# BT_AQ_DOL_R4.net
KiCad netlist of a schematic drawn in EAGLE
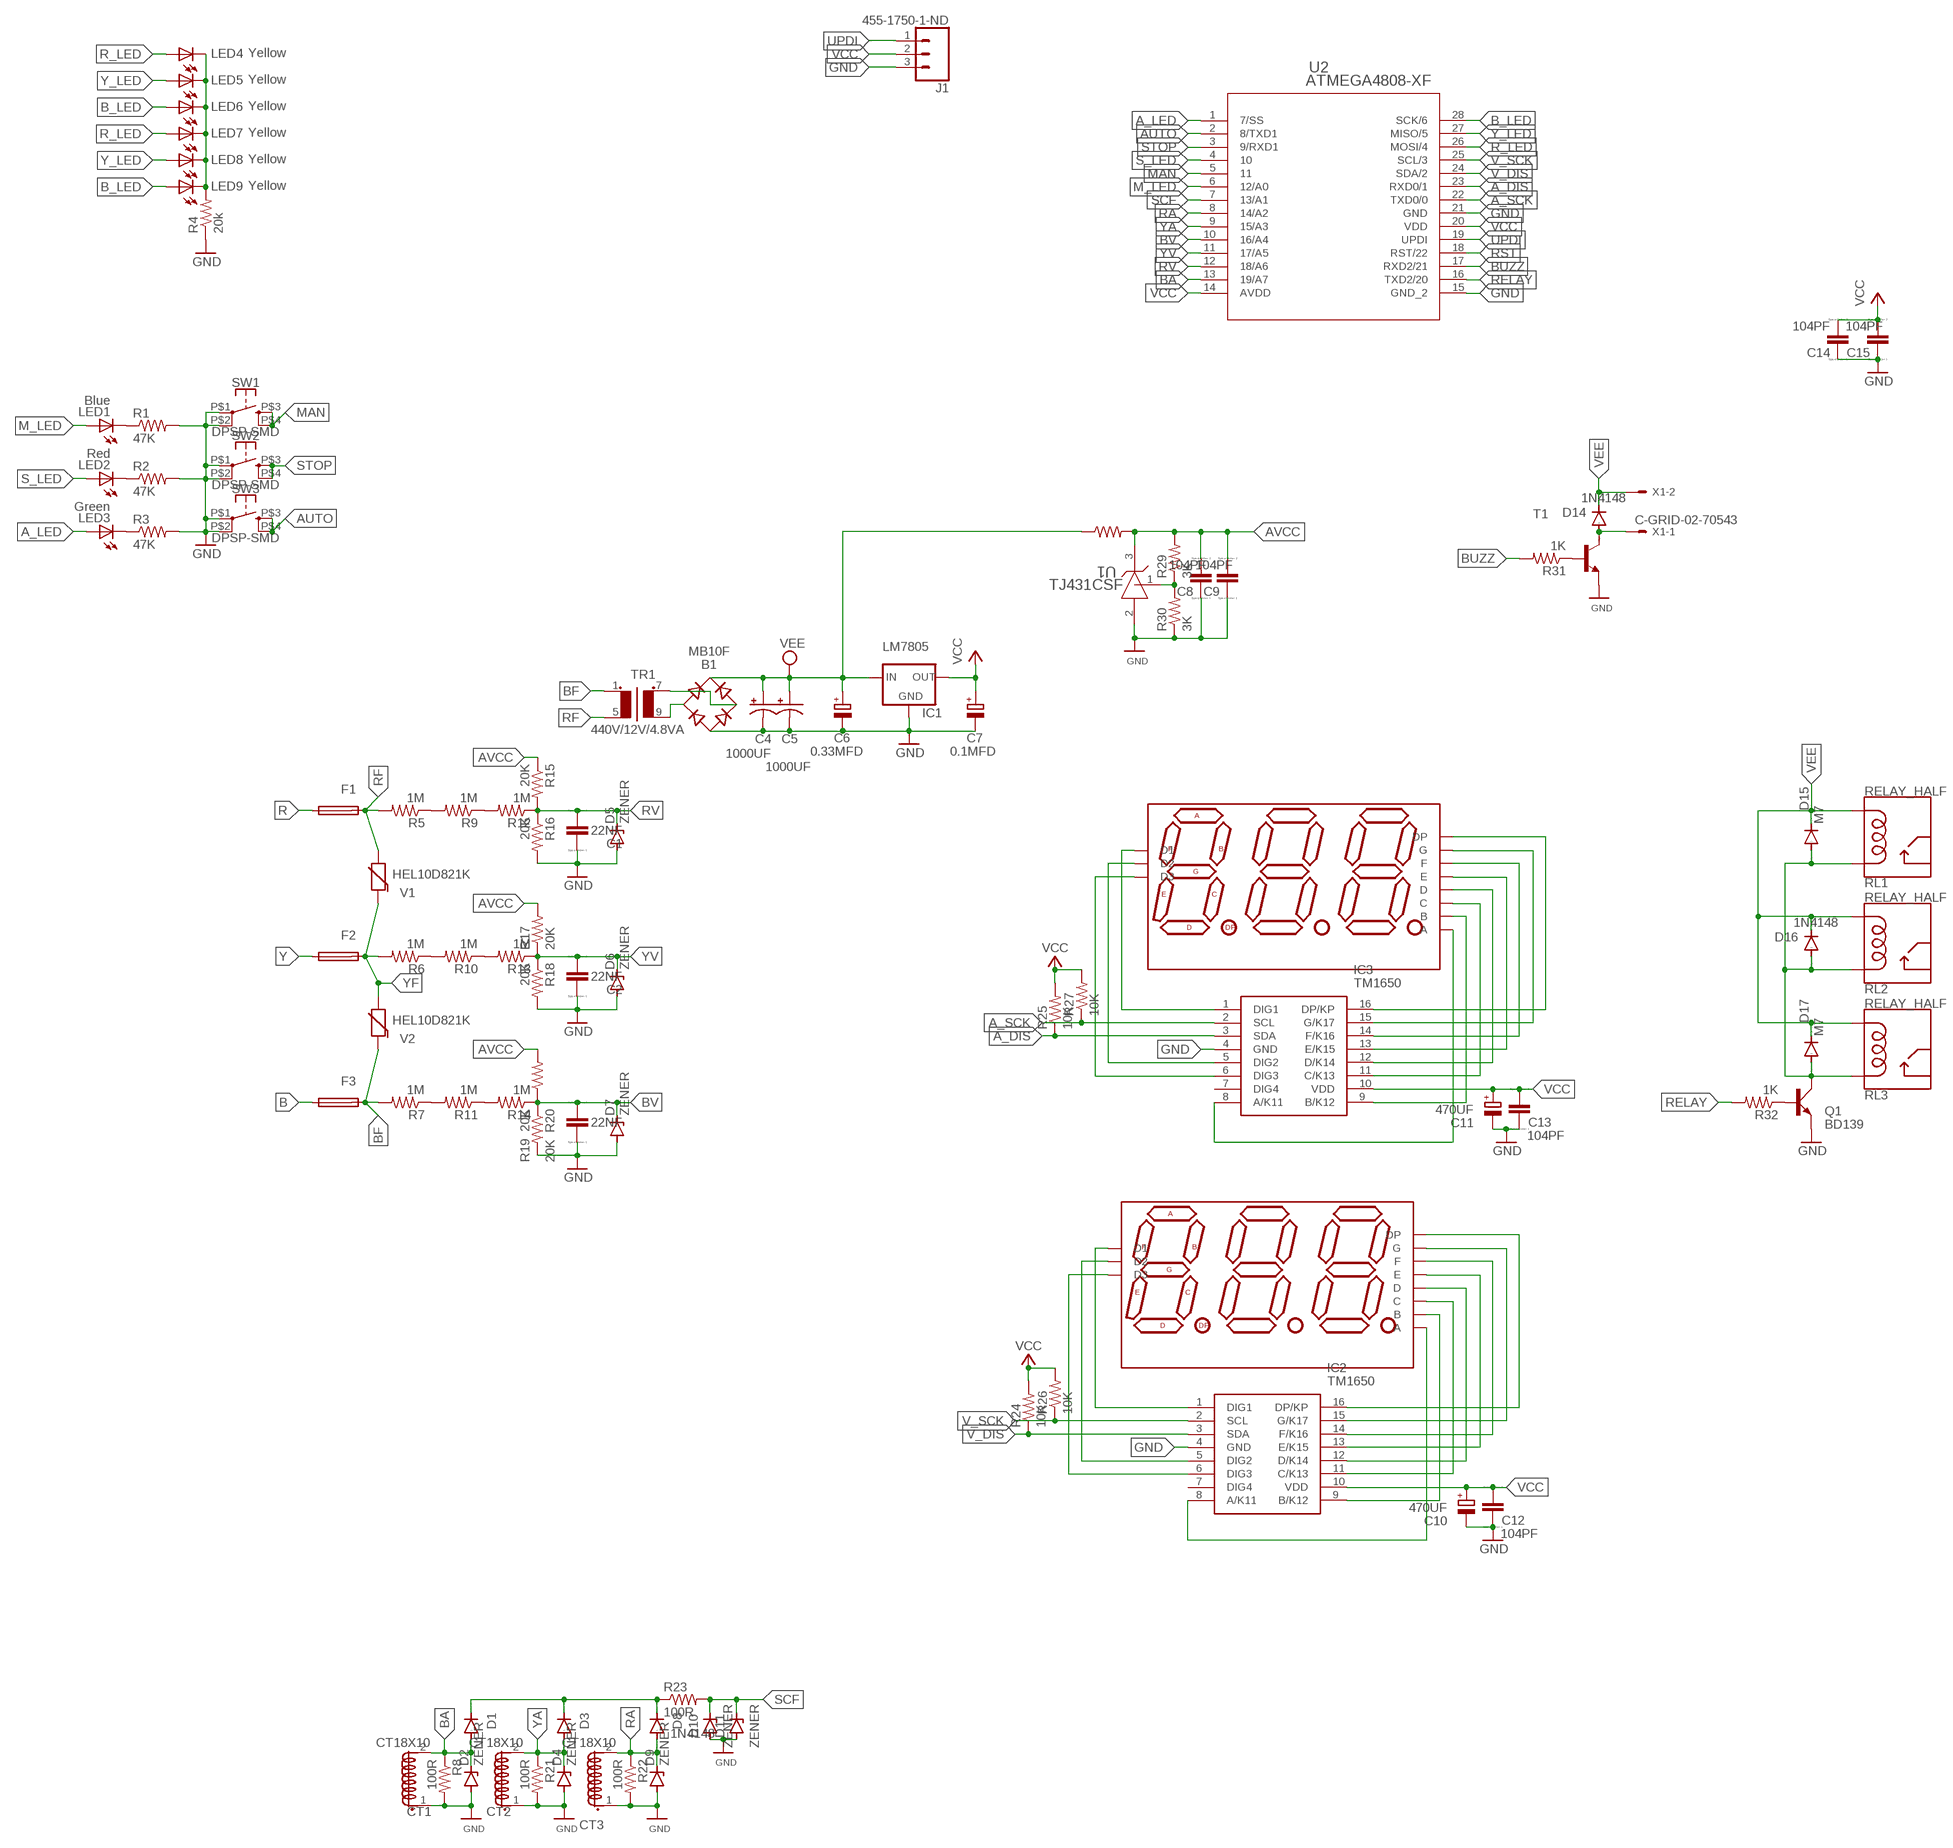
[diagram p0: schematic, sheet 1]

(export (version "E")
  (design (tool "Eeschema 10.0.6"))
  (components
    (comp (ref "B1")
      (value "MB10F")
      (footprint "eagle-import:SOIC-4")
      (libsource (lib "eagle-import") (part "MBS8"))
    )
    (comp (ref "C1")
      (value "22NF")
      (footprint "eagle-import:C1206")
      (libsource (lib "eagle-import") (part "CC1206"))
    )
    (comp (ref "C2")
      (value "22NF")
      (footprint "eagle-import:C1206")
      (libsource (lib "eagle-import") (part "CC1206"))
    )
    (comp (ref "C3")
      (value "22NF")
      (footprint "eagle-import:C1206")
      (libsource (lib "eagle-import") (part "CC1206"))
    )
    (comp (ref "C4")
      (value "1000UF")
      (footprint "eagle-import:E3,5-10")
      (libsource (lib "eagle-import") (part "CPOL-USE3.5-10"))
    )
    (comp (ref "C5")
      (value "1000UF")
      (footprint "eagle-import:E3,5-10")
      (libsource (lib "eagle-import") (part "CPOL-USE3.5-10"))
    )
    (comp (ref "C6")
      (value "0.33MFD")
      (footprint "eagle-import:E2,5-5")
      (libsource (lib "eagle-import") (part "CPOL-EUE2.5-5"))
    )
    (comp (ref "C7")
      (value "0.1MFD")
      (footprint "eagle-import:E2,5-5")
      (libsource (lib "eagle-import") (part "CPOL-EUE2.5-5"))
    )
    (comp (ref "C8")
      (value "104PF")
      (footprint "eagle-import:C1206")
      (libsource (lib "eagle-import") (part "CC1206"))
    )
    (comp (ref "C9")
      (value "104PF")
      (footprint "eagle-import:C1206")
      (libsource (lib "eagle-import") (part "CC1206"))
    )
    (comp (ref "C10")
      (value "470UF")
      (footprint "eagle-import:E3,5-8")
      (libsource (lib "eagle-import") (part "CPOL-EUE3.5-8"))
    )
    (comp (ref "C11")
      (value "470UF")
      (footprint "eagle-import:E3,5-8")
      (libsource (lib "eagle-import") (part "CPOL-EUE3.5-8"))
    )
    (comp (ref "C12")
      (value "104PF")
      (footprint "eagle-import:C1206")
      (libsource (lib "eagle-import") (part "CC1206"))
    )
    (comp (ref "C13")
      (value "104PF")
      (footprint "eagle-import:C1206")
      (libsource (lib "eagle-import") (part "CC1206"))
    )
    (comp (ref "C14")
      (value "104PF")
      (footprint "eagle-import:C1206")
      (libsource (lib "eagle-import") (part "CC1206"))
    )
    (comp (ref "C15")
      (value "104PF")
      (footprint "eagle-import:C1206")
      (libsource (lib "eagle-import") (part "CC1206"))
    )
    (comp (ref "CT1")
      (value "CT18X10")
      (footprint "eagle-import:ZMCT103C")
      (libsource (lib "eagle-import") (part "CT18X10"))
    )
    (comp (ref "CT2")
      (value "CT18X10")
      (footprint "eagle-import:ZMCT103C")
      (libsource (lib "eagle-import") (part "CT18X10"))
    )
    (comp (ref "CT3")
      (value "CT18X10")
      (footprint "eagle-import:ZMCT103C")
      (libsource (lib "eagle-import") (part "CT18X10"))
    )
    (comp (ref "D1")
      (value "1N4148")
      (footprint "eagle-import:MINIMELF")
      (libsource (lib "eagle-import") (part "DIODE-MINIMELF"))
    )
    (comp (ref "D2")
      (value "ZENER")
      (footprint "eagle-import:SOD6126X350")
      (libsource (lib "eagle-import") (part "ZENER_DO-215-BA_"))
    )
    (comp (ref "D3")
      (value "1N4148")
      (footprint "eagle-import:MINIMELF")
      (libsource (lib "eagle-import") (part "DIODE-MINIMELF"))
    )
    (comp (ref "D4")
      (value "ZENER")
      (footprint "eagle-import:SOD6126X350")
      (libsource (lib "eagle-import") (part "ZENER_DO-215-BA_"))
    )
    (comp (ref "D5")
      (value "ZENER")
      (footprint "eagle-import:SOD6126X350")
      (libsource (lib "eagle-import") (part "ZENER_DO-215-BA_"))
    )
    (comp (ref "D6")
      (value "ZENER")
      (footprint "eagle-import:SOD6126X350")
      (libsource (lib "eagle-import") (part "ZENER_DO-215-BA_"))
    )
    (comp (ref "D7")
      (value "ZENER")
      (footprint "eagle-import:SOD6126X350")
      (libsource (lib "eagle-import") (part "ZENER_DO-215-BA_"))
    )
    (comp (ref "D8")
      (value "1N4148")
      (footprint "eagle-import:MINIMELF")
      (libsource (lib "eagle-import") (part "DIODE-MINIMELF"))
    )
    (comp (ref "D9")
      (value "ZENER")
      (footprint "eagle-import:SOD6126X350")
      (libsource (lib "eagle-import") (part "ZENER_DO-215-BA_"))
    )
    (comp (ref "D10")
      (value "ZENER")
      (footprint "eagle-import:SOD6126X350")
      (libsource (lib "eagle-import") (part "ZENER_DO-215-BA_"))
    )
    (comp (ref "D11")
      (value "ZENER")
      (footprint "eagle-import:DIOMELF3516")
      (libsource (lib "eagle-import") (part "ZENER_DO-213AA(SOD-80)_"))
    )
    (comp (ref "D12")
      (value "SUNR036CC3D")
      (footprint "eagle-import:7S3D036_DIP")
      (libsource (lib "eagle-import") (part "7SEGMENT-3DIGITDIP"))
    )
    (comp (ref "D13")
      (value "SUNR036CC3D")
      (footprint "eagle-import:7S3D036_DIP")
      (libsource (lib "eagle-import") (part "7SEGMENT-3DIGITDIP"))
    )
    (comp (ref "D14")
      (value "1N4148")
      (footprint "eagle-import:MINIMELF")
      (libsource (lib "eagle-import") (part "DIODE-MINIMELF"))
    )
    (comp (ref "D15")
      (value "M7")
      (footprint "eagle-import:DO-214AC")
      (libsource (lib "eagle-import") (part "DIODE-DO-214AC"))
    )
    (comp (ref "D16")
      (value "1N4148")
      (footprint "eagle-import:MINIMELF")
      (libsource (lib "eagle-import") (part "DIODE-MINIMELF"))
    )
    (comp (ref "D17")
      (value "M7")
      (footprint "eagle-import:DO-214AC")
      (libsource (lib "eagle-import") (part "DIODE-DO-214AC"))
    )
    (comp (ref "F1")
      (value "TRF600-150")
      (footprint "eagle-import:TRF600-150")
      (libsource (lib "eagle-import") (part "PPTCPTH"))
    )
    (comp (ref "F2")
      (value "TRF600-150")
      (footprint "eagle-import:TRF600-150")
      (libsource (lib "eagle-import") (part "PPTCPTH"))
    )
    (comp (ref "F3")
      (value "TRF600-150")
      (footprint "eagle-import:TRF600-150")
      (libsource (lib "eagle-import") (part "PPTCPTH"))
    )
    (comp (ref "IC1")
      (value "LM7805")
      (footprint "eagle-import:78XXS")
      (libsource (lib "eagle-import") (part "78XXS"))
    )
    (comp (ref "IC2")
      (value "TM1650")
      (footprint "eagle-import:SOIC127P604X185-16N")
      (fields (field (name "MANUFACTURER_PART_NUMBER") "tm1650"))
      (libsource (lib "eagle-import") (part "TM1650"))
    )
    (comp (ref "IC3")
      (value "TM1650")
      (footprint "eagle-import:SOIC127P604X185-16N")
      (fields (field (name "MANUFACTURER_PART_NUMBER") "tm1650"))
      (libsource (lib "eagle-import") (part "TM1650"))
    )
    (comp (ref "J1")
      (value "455-1750-1-ND")
      (footprint "eagle-import:1X03")
      (libsource (lib "eagle-import") (part "CONN_03"))
    )
    (comp (ref "LED1")
      (value "Blue")
      (footprint "eagle-import:LED3MM")
      (libsource (lib "eagle-import") (part "LED3MM"))
    )
    (comp (ref "LED2")
      (value "Red")
      (footprint "eagle-import:LED3MM")
      (libsource (lib "eagle-import") (part "LED3MM"))
    )
    (comp (ref "LED3")
      (value "Green")
      (footprint "eagle-import:LED3MM")
      (libsource (lib "eagle-import") (part "LED3MM"))
    )
    (comp (ref "LED4")
      (value "Yellow")
      (footprint "eagle-import:LED3MM")
      (libsource (lib "eagle-import") (part "LED3MM"))
    )
    (comp (ref "LED5")
      (value "Yellow")
      (footprint "eagle-import:LED3MM")
      (libsource (lib "eagle-import") (part "LED3MM"))
    )
    (comp (ref "LED6")
      (value "Yellow")
      (footprint "eagle-import:LED3MM")
      (libsource (lib "eagle-import") (part "LED3MM"))
    )
    (comp (ref "LED7")
      (value "Yellow")
      (footprint "eagle-import:LED3MM")
      (libsource (lib "eagle-import") (part "LED3MM"))
    )
    (comp (ref "LED8")
      (value "Yellow")
      (footprint "eagle-import:LED3MM")
      (libsource (lib "eagle-import") (part "LED3MM"))
    )
    (comp (ref "LED9")
      (value "Yellow")
      (footprint "eagle-import:LED3MM")
      (libsource (lib "eagle-import") (part "LED3MM"))
    )
    (comp (ref "Q1")
      (value "BD139")
      (footprint "eagle-import:TO126AV")
      (libsource (lib "eagle-import") (part "BD139"))
    )
    (comp (ref "R1")
      (value "47K")
      (footprint "eagle-import:M1206")
      (libsource (lib "eagle-import") (part "rcl_334_R-US_M1206"))
    )
    (comp (ref "R2")
      (value "47K")
      (footprint "eagle-import:M1206")
      (libsource (lib "eagle-import") (part "rcl_334_R-US_M1206"))
    )
    (comp (ref "R3")
      (value "47K")
      (footprint "eagle-import:M1206")
      (libsource (lib "eagle-import") (part "rcl_334_R-US_M1206"))
    )
    (comp (ref "R4")
      (value "20k")
      (footprint "eagle-import:M1206")
      (libsource (lib "eagle-import") (part "rcl_334_R-US_M1206"))
    )
    (comp (ref "R5")
      (value "1M")
      (footprint "eagle-import:M1206")
      (libsource (lib "eagle-import") (part "rcl_334_R-US_M1206"))
    )
    (comp (ref "R6")
      (value "1M")
      (footprint "eagle-import:M1206")
      (libsource (lib "eagle-import") (part "rcl_334_R-US_M1206"))
    )
    (comp (ref "R7")
      (value "1M")
      (footprint "eagle-import:M1206")
      (libsource (lib "eagle-import") (part "rcl_334_R-US_M1206"))
    )
    (comp (ref "R8")
      (value "100R")
      (footprint "eagle-import:M1206")
      (libsource (lib "eagle-import") (part "R-US_M1206"))
    )
    (comp (ref "R9")
      (value "1M")
      (footprint "eagle-import:M1206")
      (libsource (lib "eagle-import") (part "rcl_334_R-US_M1206"))
    )
    (comp (ref "R10")
      (value "1M")
      (footprint "eagle-import:M1206")
      (libsource (lib "eagle-import") (part "rcl_334_R-US_M1206"))
    )
    (comp (ref "R11")
      (value "1M")
      (footprint "eagle-import:M1206")
      (libsource (lib "eagle-import") (part "rcl_334_R-US_M1206"))
    )
    (comp (ref "R12")
      (value "1M")
      (footprint "eagle-import:M1206")
      (libsource (lib "eagle-import") (part "rcl_334_R-US_M1206"))
    )
    (comp (ref "R13")
      (value "1M")
      (footprint "eagle-import:M1206")
      (libsource (lib "eagle-import") (part "rcl_334_R-US_M1206"))
    )
    (comp (ref "R14")
      (value "1M")
      (footprint "eagle-import:M1206")
      (libsource (lib "eagle-import") (part "rcl_334_R-US_M1206"))
    )
    (comp (ref "R15")
      (value "20K")
      (footprint "eagle-import:M1206")
      (libsource (lib "eagle-import") (part "rcl_334_R-US_M1206"))
    )
    (comp (ref "R16")
      (value "20K")
      (footprint "eagle-import:M1206")
      (libsource (lib "eagle-import") (part "rcl_334_R-US_M1206"))
    )
    (comp (ref "R17")
      (value "20K")
      (footprint "eagle-import:M1206")
      (libsource (lib "eagle-import") (part "rcl_334_R-US_M1206"))
    )
    (comp (ref "R18")
      (value "20K")
      (footprint "eagle-import:M1206")
      (libsource (lib "eagle-import") (part "rcl_334_R-US_M1206"))
    )
    (comp (ref "R19")
      (value "20K")
      (footprint "eagle-import:M1206")
      (libsource (lib "eagle-import") (part "rcl_334_R-US_M1206"))
    )
    (comp (ref "R20")
      (value "20K")
      (footprint "eagle-import:M1206")
      (libsource (lib "eagle-import") (part "rcl_334_R-US_M1206"))
    )
    (comp (ref "R21")
      (value "100R")
      (footprint "eagle-import:M1206")
      (libsource (lib "eagle-import") (part "R-US_M1206"))
    )
    (comp (ref "R22")
      (value "100R")
      (footprint "eagle-import:M1206")
      (libsource (lib "eagle-import") (part "R-US_M1206"))
    )
    (comp (ref "R23")
      (value "100R")
      (footprint "eagle-import:M1206")
      (libsource (lib "eagle-import") (part "R-US_M1206"))
    )
    (comp (ref "R24")
      (value "10K")
      (footprint "eagle-import:M1206")
      (libsource (lib "eagle-import") (part "rcl_334_R-US_M1206"))
    )
    (comp (ref "R25")
      (value "10K")
      (footprint "eagle-import:M1206")
      (libsource (lib "eagle-import") (part "rcl_334_R-US_M1206"))
    )
    (comp (ref "R26")
      (value "10K")
      (footprint "eagle-import:M1206")
      (libsource (lib "eagle-import") (part "rcl_334_R-US_M1206"))
    )
    (comp (ref "R27")
      (value "10K")
      (footprint "eagle-import:M1206")
      (libsource (lib "eagle-import") (part "rcl_334_R-US_M1206"))
    )
    (comp (ref "R28")
      (value "10K")
      (footprint "eagle-import:M1206")
      (libsource (lib "eagle-import") (part "R-US_M1206"))
    )
    (comp (ref "R29")
      (value "3K")
      (footprint "eagle-import:M1206")
      (libsource (lib "eagle-import") (part "R-US_M1206"))
    )
    (comp (ref "R30")
      (value "3K")
      (footprint "eagle-import:M1206")
      (libsource (lib "eagle-import") (part "R-US_M1206"))
    )
    (comp (ref "R31")
      (value "1K")
      (footprint "eagle-import:M1206")
      (libsource (lib "eagle-import") (part "rcl_334_R-US_M1206"))
    )
    (comp (ref "R32")
      (value "1K")
      (footprint "eagle-import:M1206")
      (libsource (lib "eagle-import") (part "rcl_334_R-US_M1206"))
    )
    (comp (ref "RL1")
      (value "RELAY_HALF")
      (footprint "eagle-import:DT90_HALF")
      (libsource (lib "eagle-import") (part "RELAY_HALF"))
    )
    (comp (ref "RL2")
      (value "RELAY_HALF")
      (footprint "eagle-import:DT90_HALF")
      (libsource (lib "eagle-import") (part "RELAY_HALF"))
    )
    (comp (ref "RL3")
      (value "RELAY_HALF")
      (footprint "eagle-import:DT90_HALF")
      (libsource (lib "eagle-import") (part "RELAY_HALF"))
    )
    (comp (ref "SW1")
      (value "DPSP-SMD")
      (footprint "eagle-import:B3F-40XX-ROUND-SMD")
      (libsource (lib "eagle-import") (part "DPSP-SMD"))
    )
    (comp (ref "SW2")
      (value "DPSP-SMD")
      (footprint "eagle-import:B3F-40XX-ROUND-SMD")
      (libsource (lib "eagle-import") (part "DPSP-SMD"))
    )
    (comp (ref "SW3")
      (value "DPSP-SMD")
      (footprint "eagle-import:B3F-40XX-ROUND-SMD")
      (libsource (lib "eagle-import") (part "DPSP-SMD"))
    )
    (comp (ref "T1")
      (value "MMUN2213LT1-NPN-SC59-BEC")
      (footprint "eagle-import:SC59-BEC")
      (libsource (lib "eagle-import") (part "-NPN-SC59-BECMMUN2213LT1"))
    )
    (comp (ref "TR1")
      (value "440V/12V/4.8VA")
      (footprint "eagle-import:440V12V6VA")
      (libsource (lib "eagle-import") (part "TRANSFORMER6VA"))
    )
    (comp (ref "U1")
      (value "TJ431CSF")
      (footprint "eagle-import:SOT-23")
      (fields
        (field (name "MANUFACTURER_PART_NUMBER") "TL431IDBZTG4")
        (field (name "COPYRIGHT") "Copyright (C) 2022 Ultra Librarian. All rights reserved.")
      )
      (libsource (lib "eagle-import") (part "TJ431CSFDBZ0003A_L"))
    )
    (comp (ref "U2")
      (value "ATMEGA4808-XF")
      (footprint "eagle-import:SSOP28_SS_MCH")
      (fields (field (name "COPYRIGHT") "Copyright (C) 2022 Ultra Librarian. All rights reserved."))
      (libsource (lib "eagle-import") (part "ATMEGA4808-XF"))
    )
    (comp (ref "V1")
      (value "HEL10D821K")
      (footprint "eagle-import:10MM")
      (libsource (lib "eagle-import") (part "VARISTOR"))
    )
    (comp (ref "V2")
      (value "HEL10D821K")
      (footprint "eagle-import:10MM")
      (libsource (lib "eagle-import") (part "VARISTOR"))
    )
    (comp (ref "X1")
      (value "C-GRID-02-70543")
      (footprint "eagle-import:70543-02")
      (fields (field (name "MF") "MOLEX"))
      (libsource (lib "eagle-import") (part "C-GRID-02-70543"))
    )
  )
  (nets
    (net (code "1") (name "AUTO") (class "Default")
      (node (ref "SW3") (pin "P$3") (pinfunction "3_P$3") (pintype "passive"))
      (node (ref "SW3") (pin "P$4") (pinfunction "4_P$4") (pintype "passive"))
      (node (ref "U2") (pin "2") (pinfunction "8/TXD1_2") (pintype "bidirectional"))
    )
    (net (code "2") (name "AVCC") (class "Default")
      (node (ref "C8") (pin "2") (pinfunction "2_2") (pintype "passive"))
      (node (ref "C9") (pin "2") (pinfunction "2_2") (pintype "passive"))
      (node (ref "R15") (pin "1") (pinfunction "1_1") (pintype "passive"))
      (node (ref "R17") (pin "2") (pinfunction "2_2") (pintype "passive"))
      (node (ref "R19") (pin "2") (pinfunction "2_2") (pintype "passive"))
      (node (ref "R28") (pin "2") (pinfunction "2_2") (pintype "passive"))
      (node (ref "R29") (pin "2") (pinfunction "2_2") (pintype "passive"))
      (node (ref "U1") (pin "3") (pinfunction "CATHODE_3") (pintype "passive"))
    )
    (net (code "3") (name "A_DIS") (class "Default")
      (node (ref "IC3") (pin "3") (pinfunction "SDA_3") (pintype "input"))
      (node (ref "R25") (pin "1") (pinfunction "1_1") (pintype "passive"))
      (node (ref "U2") (pin "23") (pinfunction "RXD0/1_23") (pintype "bidirectional"))
    )
    (net (code "4") (name "A_LED") (class "Default")
      (node (ref "LED3") (pin "A") (pinfunction "A_A") (pintype "passive"))
      (node (ref "U2") (pin "1") (pinfunction "7/SS_1") (pintype "bidirectional"))
    )
    (net (code "5") (name "A_SCK") (class "Default")
      (node (ref "IC3") (pin "2") (pinfunction "SCL_2") (pintype "input"))
      (node (ref "R27") (pin "1") (pinfunction "1_1") (pintype "passive"))
      (node (ref "U2") (pin "22") (pinfunction "TXD0/0_22") (pintype "bidirectional"))
    )
    (net (code "6") (name "B") (class "Default")
      (node (ref "F3") (pin "1") (pinfunction "1_1") (pintype "passive"))
    )
    (net (code "7") (name "BA") (class "Default")
      (node (ref "CT1") (pin "2") (pinfunction "S1.2_2") (pintype "passive"))
      (node (ref "D1") (pin "A") (pinfunction "A_A") (pintype "passive"))
      (node (ref "D2") (pin "1") (pinfunction "C_1") (pintype "passive"))
      (node (ref "R8") (pin "1") (pinfunction "1_1") (pintype "passive"))
      (node (ref "U2") (pin "13") (pinfunction "19/A7_13") (pintype "bidirectional"))
    )
    (net (code "8") (name "BF") (class "Default")
      (node (ref "F3") (pin "2") (pinfunction "2_2") (pintype "passive"))
      (node (ref "R7") (pin "2") (pinfunction "2_2") (pintype "passive"))
      (node (ref "TR1") (pin "1") (pinfunction "P1_1") (pintype "passive"))
      (node (ref "V2") (pin "1") (pinfunction "1_1") (pintype "passive"))
    )
    (net (code "9") (name "BUZZ") (class "Default")
      (node (ref "R31") (pin "2") (pinfunction "2_2") (pintype "passive"))
      (node (ref "U2") (pin "17") (pinfunction "RXD2/21_17") (pintype "bidirectional"))
    )
    (net (code "10") (name "BV") (class "Default")
      (node (ref "C3") (pin "2") (pinfunction "2_2") (pintype "passive"))
      (node (ref "D7") (pin "1") (pinfunction "C_1") (pintype "passive"))
      (node (ref "R14") (pin "1") (pinfunction "1_1") (pintype "passive"))
      (node (ref "R19") (pin "1") (pinfunction "1_1") (pintype "passive"))
      (node (ref "R20") (pin "1") (pinfunction "1_1") (pintype "passive"))
      (node (ref "U2") (pin "10") (pinfunction "16/A4_10") (pintype "bidirectional"))
    )
    (net (code "11") (name "B_LED") (class "Default")
      (node (ref "LED6") (pin "A") (pinfunction "A_A") (pintype "passive"))
      (node (ref "LED9") (pin "A") (pinfunction "A_A") (pintype "passive"))
      (node (ref "U2") (pin "28") (pinfunction "SCK/6_28") (pintype "bidirectional"))
    )
    (net (code "12") (name "GND") (class "Default")
      (node (ref "B1") (pin "-") (pinfunction "-_-") (pintype "passive"))
      (node (ref "C1") (pin "1") (pinfunction "1_1") (pintype "passive"))
      (node (ref "C10") (pin "-") (pinfunction "-_-") (pintype "passive"))
      (node (ref "C11") (pin "-") (pinfunction "-_-") (pintype "passive"))
      (node (ref "C12") (pin "1") (pinfunction "1_1") (pintype "passive"))
      (node (ref "C13") (pin "1") (pinfunction "1_1") (pintype "passive"))
      (node (ref "C14") (pin "1") (pinfunction "1_1") (pintype "passive"))
      (node (ref "C15") (pin "1") (pinfunction "1_1") (pintype "passive"))
      (node (ref "C2") (pin "1") (pinfunction "1_1") (pintype "passive"))
      (node (ref "C3") (pin "1") (pinfunction "1_1") (pintype "passive"))
      (node (ref "C4") (pin "-") (pinfunction "-_-") (pintype "passive"))
      (node (ref "C5") (pin "-") (pinfunction "-_-") (pintype "passive"))
      (node (ref "C6") (pin "-") (pinfunction "-_-") (pintype "passive"))
      (node (ref "C7") (pin "-") (pinfunction "-_-") (pintype "passive"))
      (node (ref "C8") (pin "1") (pinfunction "1_1") (pintype "passive"))
      (node (ref "C9") (pin "1") (pinfunction "1_1") (pintype "passive"))
      (node (ref "CT1") (pin "1") (pinfunction "S1.1_1") (pintype "passive"))
      (node (ref "CT2") (pin "1") (pinfunction "S1.1_1") (pintype "passive"))
      (node (ref "CT3") (pin "1") (pinfunction "S1.1_1") (pintype "passive"))
      (node (ref "D10") (pin "2") (pinfunction "A_2") (pintype "passive"))
      (node (ref "D11") (pin "2") (pinfunction "A_2") (pintype "passive"))
      (node (ref "D2") (pin "2") (pinfunction "A_2") (pintype "passive"))
      (node (ref "D4") (pin "2") (pinfunction "A_2") (pintype "passive"))
      (node (ref "D5") (pin "2") (pinfunction "A_2") (pintype "passive"))
      (node (ref "D6") (pin "2") (pinfunction "A_2") (pintype "passive"))
      (node (ref "D7") (pin "2") (pinfunction "A_2") (pintype "passive"))
      (node (ref "D9") (pin "2") (pinfunction "A_2") (pintype "passive"))
      (node (ref "IC1") (pin "GND") (pinfunction "GND_GND") (pintype "input"))
      (node (ref "IC2") (pin "4") (pinfunction "GND_4") (pintype "power_in"))
      (node (ref "IC3") (pin "4") (pinfunction "GND_4") (pintype "power_in"))
      (node (ref "J1") (pin "3") (pinfunction "3_3") (pintype "passive"))
      (node (ref "Q1") (pin "E") (pinfunction "E_E") (pintype "passive"))
      (node (ref "R1") (pin "2") (pinfunction "2_2") (pintype "passive"))
      (node (ref "R16") (pin "2") (pinfunction "2_2") (pintype "passive"))
      (node (ref "R18") (pin "2") (pinfunction "2_2") (pintype "passive"))
      (node (ref "R2") (pin "2") (pinfunction "2_2") (pintype "passive"))
      (node (ref "R20") (pin "2") (pinfunction "2_2") (pintype "passive"))
      (node (ref "R21") (pin "2") (pinfunction "2_2") (pintype "passive"))
      (node (ref "R22") (pin "2") (pinfunction "2_2") (pintype "passive"))
      (node (ref "R3") (pin "2") (pinfunction "2_2") (pintype "passive"))
      (node (ref "R30") (pin "1") (pinfunction "1_1") (pintype "passive"))
      (node (ref "R4") (pin "1") (pinfunction "1_1") (pintype "passive"))
      (node (ref "R8") (pin "2") (pinfunction "2_2") (pintype "passive"))
      (node (ref "SW1") (pin "P$1") (pinfunction "1_P$1") (pintype "passive"))
      (node (ref "SW1") (pin "P$2") (pinfunction "2_P$2") (pintype "passive"))
      (node (ref "SW2") (pin "P$1") (pinfunction "1_P$1") (pintype "passive"))
      (node (ref "SW2") (pin "P$2") (pinfunction "2_P$2") (pintype "passive"))
      (node (ref "SW3") (pin "P$1") (pinfunction "1_P$1") (pintype "passive"))
      (node (ref "SW3") (pin "P$2") (pinfunction "2_P$2") (pintype "passive"))
      (node (ref "T1") (pin "E") (pinfunction "E_E") (pintype "passive"))
      (node (ref "U1") (pin "2") (pinfunction "ANODE_2") (pintype "passive"))
      (node (ref "U2") (pin "15") (pinfunction "GND_2_15") (pintype "passive"))
      (node (ref "U2") (pin "21") (pinfunction "GND_21") (pintype "passive"))
    )
    (net (code "13") (name "MAN") (class "Default")
      (node (ref "SW1") (pin "P$3") (pinfunction "3_P$3") (pintype "passive"))
      (node (ref "SW1") (pin "P$4") (pinfunction "4_P$4") (pintype "passive"))
      (node (ref "U2") (pin "5") (pinfunction "11_5") (pintype "bidirectional"))
    )
    (net (code "14") (name "M_LED") (class "Default")
      (node (ref "LED1") (pin "A") (pinfunction "A_A") (pintype "passive"))
      (node (ref "U2") (pin "6") (pinfunction "12/A0_6") (pintype "bidirectional"))
    )
    (net (code "15") (name "Net-(B1-AC1)") (class "Default")
      (node (ref "B1") (pin "~1") (pinfunction "AC1_~1") (pintype "passive"))
      (node (ref "TR1") (pin "9") (pinfunction "S2_9") (pintype "passive"))
    )
    (net (code "16") (name "Net-(B1-AC2)") (class "Default")
      (node (ref "B1") (pin "~2") (pinfunction "AC2_~2") (pintype "passive"))
      (node (ref "TR1") (pin "7") (pinfunction "S1_7") (pintype "passive"))
    )
    (net (code "17") (name "Net-(D1-PadC)") (class "Default")
      (node (ref "D1") (pin "C") (pinfunction "C_C") (pintype "passive"))
      (node (ref "D3") (pin "C") (pinfunction "C_C") (pintype "passive"))
      (node (ref "D8") (pin "C") (pinfunction "C_C") (pintype "passive"))
      (node (ref "R23") (pin "1") (pinfunction "1_1") (pintype "passive"))
    )
    (net (code "18") (name "Net-(D12-A)") (class "Default")
      (node (ref "D12") (pin "11") (pinfunction "A_11") (pintype "bidirectional"))
      (node (ref "IC2") (pin "8") (pinfunction "A/K11_8") (pintype "bidirectional"))
    )
    (net (code "19") (name "Net-(D12-B)") (class "Default")
      (node (ref "D12") (pin "7") (pinfunction "B_7") (pintype "bidirectional"))
      (node (ref "IC2") (pin "9") (pinfunction "B/K12_9") (pintype "bidirectional"))
    )
    (net (code "20") (name "Net-(D12-C)") (class "Default")
      (node (ref "D12") (pin "4") (pinfunction "C_4") (pintype "bidirectional"))
      (node (ref "IC2") (pin "11") (pinfunction "C/K13_11") (pintype "bidirectional"))
    )
    (net (code "21") (name "Net-(D12-D)") (class "Default")
      (node (ref "D12") (pin "2") (pinfunction "D_2") (pintype "bidirectional"))
      (node (ref "IC2") (pin "12") (pinfunction "D/K14_12") (pintype "bidirectional"))
    )
    (net (code "22") (name "Net-(D12-D1)") (class "Default")
      (node (ref "D12") (pin "12") (pinfunction "D1_12") (pintype "bidirectional"))
      (node (ref "IC2") (pin "1") (pinfunction "DIG1_1") (pintype "bidirectional"))
    )
    (net (code "23") (name "Net-(D12-D2)") (class "Default")
      (node (ref "D12") (pin "9") (pinfunction "D2_9") (pintype "bidirectional"))
      (node (ref "IC2") (pin "5") (pinfunction "DIG2_5") (pintype "bidirectional"))
    )
    (net (code "24") (name "Net-(D12-D3)") (class "Default")
      (node (ref "D12") (pin "8") (pinfunction "D3_8") (pintype "bidirectional"))
      (node (ref "IC2") (pin "6") (pinfunction "DIG3_6") (pintype "bidirectional"))
    )
    (net (code "25") (name "Net-(D12-DP)") (class "Default")
      (node (ref "D12") (pin "3") (pinfunction "DP_3") (pintype "bidirectional"))
      (node (ref "IC2") (pin "16") (pinfunction "DP/KP_16") (pintype "bidirectional"))
    )
    (net (code "26") (name "Net-(D12-E)") (class "Default")
      (node (ref "D12") (pin "1") (pinfunction "E_1") (pintype "bidirectional"))
      (node (ref "IC2") (pin "13") (pinfunction "E/K15_13") (pintype "bidirectional"))
    )
    (net (code "27") (name "Net-(D12-F)") (class "Default")
      (node (ref "D12") (pin "10") (pinfunction "F_10") (pintype "bidirectional"))
      (node (ref "IC2") (pin "14") (pinfunction "F/K16_14") (pintype "bidirectional"))
    )
    (net (code "28") (name "Net-(D12-G)") (class "Default")
      (node (ref "D12") (pin "5") (pinfunction "G_5") (pintype "bidirectional"))
      (node (ref "IC2") (pin "15") (pinfunction "G/K17_15") (pintype "bidirectional"))
    )
    (net (code "29") (name "Net-(D13-A)") (class "Default")
      (node (ref "D13") (pin "11") (pinfunction "A_11") (pintype "bidirectional"))
      (node (ref "IC3") (pin "8") (pinfunction "A/K11_8") (pintype "bidirectional"))
    )
    (net (code "30") (name "Net-(D13-B)") (class "Default")
      (node (ref "D13") (pin "7") (pinfunction "B_7") (pintype "bidirectional"))
      (node (ref "IC3") (pin "9") (pinfunction "B/K12_9") (pintype "bidirectional"))
    )
    (net (code "31") (name "Net-(D13-C)") (class "Default")
      (node (ref "D13") (pin "4") (pinfunction "C_4") (pintype "bidirectional"))
      (node (ref "IC3") (pin "11") (pinfunction "C/K13_11") (pintype "bidirectional"))
    )
    (net (code "32") (name "Net-(D13-D)") (class "Default")
      (node (ref "D13") (pin "2") (pinfunction "D_2") (pintype "bidirectional"))
      (node (ref "IC3") (pin "12") (pinfunction "D/K14_12") (pintype "bidirectional"))
    )
    (net (code "33") (name "Net-(D13-D1)") (class "Default")
      (node (ref "D13") (pin "12") (pinfunction "D1_12") (pintype "bidirectional"))
      (node (ref "IC3") (pin "1") (pinfunction "DIG1_1") (pintype "bidirectional"))
    )
    (net (code "34") (name "Net-(D13-D2)") (class "Default")
      (node (ref "D13") (pin "9") (pinfunction "D2_9") (pintype "bidirectional"))
      (node (ref "IC3") (pin "5") (pinfunction "DIG2_5") (pintype "bidirectional"))
    )
    (net (code "35") (name "Net-(D13-D3)") (class "Default")
      (node (ref "D13") (pin "8") (pinfunction "D3_8") (pintype "bidirectional"))
      (node (ref "IC3") (pin "6") (pinfunction "DIG3_6") (pintype "bidirectional"))
    )
    (net (code "36") (name "Net-(D13-DP)") (class "Default")
      (node (ref "D13") (pin "3") (pinfunction "DP_3") (pintype "bidirectional"))
      (node (ref "IC3") (pin "16") (pinfunction "DP/KP_16") (pintype "bidirectional"))
    )
    (net (code "37") (name "Net-(D13-E)") (class "Default")
      (node (ref "D13") (pin "1") (pinfunction "E_1") (pintype "bidirectional"))
      (node (ref "IC3") (pin "13") (pinfunction "E/K15_13") (pintype "bidirectional"))
    )
    (net (code "38") (name "Net-(D13-F)") (class "Default")
      (node (ref "D13") (pin "10") (pinfunction "F_10") (pintype "bidirectional"))
      (node (ref "IC3") (pin "14") (pinfunction "F/K16_14") (pintype "bidirectional"))
    )
    (net (code "39") (name "Net-(D13-G)") (class "Default")
      (node (ref "D13") (pin "5") (pinfunction "G_5") (pintype "bidirectional"))
      (node (ref "IC3") (pin "15") (pinfunction "G/K17_15") (pintype "bidirectional"))
    )
    (net (code "40") (name "Net-(LED1-C)") (class "Default")
      (node (ref "LED1") (pin "K") (pinfunction "C_K") (pintype "passive"))
      (node (ref "R1") (pin "1") (pinfunction "1_1") (pintype "passive"))
    )
    (net (code "41") (name "Net-(LED2-C)") (class "Default")
      (node (ref "LED2") (pin "K") (pinfunction "C_K") (pintype "passive"))
      (node (ref "R2") (pin "1") (pinfunction "1_1") (pintype "passive"))
    )
    (net (code "42") (name "Net-(LED3-C)") (class "Default")
      (node (ref "LED3") (pin "K") (pinfunction "C_K") (pintype "passive"))
      (node (ref "R3") (pin "1") (pinfunction "1_1") (pintype "passive"))
    )
    (net (code "43") (name "Net-(LED4-C)") (class "Default")
      (node (ref "LED4") (pin "K") (pinfunction "C_K") (pintype "passive"))
      (node (ref "LED5") (pin "K") (pinfunction "C_K") (pintype "passive"))
      (node (ref "LED6") (pin "K") (pinfunction "C_K") (pintype "passive"))
      (node (ref "LED7") (pin "K") (pinfunction "C_K") (pintype "passive"))
      (node (ref "LED8") (pin "K") (pinfunction "C_K") (pintype "passive"))
      (node (ref "LED9") (pin "K") (pinfunction "C_K") (pintype "passive"))
      (node (ref "R4") (pin "2") (pinfunction "2_2") (pintype "passive"))
    )
    (net (code "44") (name "Net-(Q1-PadB)") (class "Default")
      (node (ref "Q1") (pin "B") (pinfunction "B_B") (pintype "passive"))
      (node (ref "R32") (pin "1") (pinfunction "1_1") (pintype "passive"))
    )
    (net (code "45") (name "Net-(R5-Pad1)") (class "Default")
      (node (ref "R5") (pin "1") (pinfunction "1_1") (pintype "passive"))
      (node (ref "R9") (pin "2") (pinfunction "2_2") (pintype "passive"))
    )
    (net (code "46") (name "Net-(R10-Pad1)") (class "Default")
      (node (ref "R10") (pin "1") (pinfunction "1_1") (pintype "passive"))
      (node (ref "R13") (pin "2") (pinfunction "2_2") (pintype "passive"))
    )
    (net (code "47") (name "Net-(R10-Pad2)") (class "Default")
      (node (ref "R10") (pin "2") (pinfunction "2_2") (pintype "passive"))
      (node (ref "R6") (pin "1") (pinfunction "1_1") (pintype "passive"))
    )
    (net (code "48") (name "Net-(R11-Pad1)") (class "Default")
      (node (ref "R11") (pin "1") (pinfunction "1_1") (pintype "passive"))
      (node (ref "R14") (pin "2") (pinfunction "2_2") (pintype "passive"))
    )
    (net (code "49") (name "Net-(R11-Pad2)") (class "Default")
      (node (ref "R11") (pin "2") (pinfunction "2_2") (pintype "passive"))
      (node (ref "R7") (pin "1") (pinfunction "1_1") (pintype "passive"))
    )
    (net (code "50") (name "Net-(R12-Pad2)") (class "Default")
      (node (ref "R12") (pin "2") (pinfunction "2_2") (pintype "passive"))
      (node (ref "R9") (pin "1") (pinfunction "1_1") (pintype "passive"))
    )
    (net (code "51") (name "Net-(R31-Pad1)") (class "Default")
      (node (ref "R31") (pin "1") (pinfunction "1_1") (pintype "passive"))
      (node (ref "T1") (pin "B") (pinfunction "B_B") (pintype "passive"))
    )
    (net (code "52") (name "Net-(RL1-COIL1)") (class "Default")
      (node (ref "D15") (pin "A") (pinfunction "A_A") (pintype "passive"))
      (node (ref "D16") (pin "A") (pinfunction "A_A") (pintype "passive"))
      (node (ref "D17") (pin "A") (pinfunction "A_A") (pintype "passive"))
      (node (ref "Q1") (pin "C") (pinfunction "C_C") (pintype "passive"))
      (node (ref "RL1") (pin "1") (pinfunction "COIL1_1") (pintype "bidirectional"))
      (node (ref "RL2") (pin "1") (pinfunction "COIL1_1") (pintype "bidirectional"))
      (node (ref "RL3") (pin "1") (pinfunction "COIL1_1") (pintype "bidirectional"))
    )
    (net (code "53") (name "Net-(U1-REF)") (class "Default")
      (node (ref "R29") (pin "1") (pinfunction "1_1") (pintype "passive"))
      (node (ref "R30") (pin "2") (pinfunction "2_2") (pintype "passive"))
      (node (ref "U1") (pin "1") (pinfunction "REF_1") (pintype "input"))
    )
    (net (code "54") (name "Net-(X1A-S)") (class "Default")
      (node (ref "D14") (pin "A") (pinfunction "A_A") (pintype "passive"))
      (node (ref "T1") (pin "C") (pinfunction "C_C") (pintype "passive"))
      (node (ref "X1") (pin "1") (pinfunction "S_1") (pintype "passive"))
    )
    (net (code "55") (name "R") (class "Default")
      (node (ref "F1") (pin "1") (pinfunction "1_1") (pintype "passive"))
    )
    (net (code "56") (name "RA") (class "Default")
      (node (ref "CT3") (pin "2") (pinfunction "S1.2_2") (pintype "passive"))
      (node (ref "D8") (pin "A") (pinfunction "A_A") (pintype "passive"))
      (node (ref "D9") (pin "1") (pinfunction "C_1") (pintype "passive"))
      (node (ref "R22") (pin "1") (pinfunction "1_1") (pintype "passive"))
      (node (ref "U2") (pin "8") (pinfunction "14/A2_8") (pintype "bidirectional"))
    )
    (net (code "57") (name "RELAY") (class "Default")
      (node (ref "R32") (pin "2") (pinfunction "2_2") (pintype "passive"))
      (node (ref "U2") (pin "16") (pinfunction "TXD2/20_16") (pintype "bidirectional"))
    )
    (net (code "58") (name "RF") (class "Default")
      (node (ref "F1") (pin "2") (pinfunction "2_2") (pintype "passive"))
      (node (ref "R5") (pin "2") (pinfunction "2_2") (pintype "passive"))
      (node (ref "TR1") (pin "5") (pinfunction "P2_5") (pintype "passive"))
      (node (ref "V1") (pin "2") (pinfunction "2_2") (pintype "passive"))
    )
    (net (code "59") (name "RST") (class "Default")
      (node (ref "U2") (pin "18") (pinfunction "RST/22_18") (pintype "bidirectional"))
    )
    (net (code "60") (name "RV") (class "Default")
      (node (ref "C1") (pin "2") (pinfunction "2_2") (pintype "passive"))
      (node (ref "D5") (pin "1") (pinfunction "C_1") (pintype "passive"))
      (node (ref "R12") (pin "1") (pinfunction "1_1") (pintype "passive"))
      (node (ref "R15") (pin "2") (pinfunction "2_2") (pintype "passive"))
      (node (ref "R16") (pin "1") (pinfunction "1_1") (pintype "passive"))
      (node (ref "U2") (pin "12") (pinfunction "18/A6_12") (pintype "bidirectional"))
    )
    (net (code "61") (name "R_LED") (class "Default")
      (node (ref "LED4") (pin "A") (pinfunction "A_A") (pintype "passive"))
      (node (ref "LED7") (pin "A") (pinfunction "A_A") (pintype "passive"))
      (node (ref "U2") (pin "26") (pinfunction "MOSI/4_26") (pintype "bidirectional"))
    )
    (net (code "62") (name "SCF") (class "Default")
      (node (ref "D10") (pin "1") (pinfunction "C_1") (pintype "passive"))
      (node (ref "D11") (pin "1") (pinfunction "C_1") (pintype "passive"))
      (node (ref "R23") (pin "2") (pinfunction "2_2") (pintype "passive"))
      (node (ref "U2") (pin "7") (pinfunction "13/A1_7") (pintype "bidirectional"))
    )
    (net (code "63") (name "STOP") (class "Default")
      (node (ref "SW2") (pin "P$3") (pinfunction "3_P$3") (pintype "passive"))
      (node (ref "SW2") (pin "P$4") (pinfunction "4_P$4") (pintype "passive"))
      (node (ref "U2") (pin "3") (pinfunction "9/RXD1_3") (pintype "bidirectional"))
    )
    (net (code "64") (name "S_LED") (class "Default")
      (node (ref "LED2") (pin "A") (pinfunction "A_A") (pintype "passive"))
      (node (ref "U2") (pin "4") (pinfunction "10_4") (pintype "bidirectional"))
    )
    (net (code "65") (name "UPDI") (class "Default")
      (node (ref "J1") (pin "1") (pinfunction "1_1") (pintype "passive"))
      (node (ref "U2") (pin "19") (pinfunction "UPDI_19") (pintype "bidirectional"))
    )
    (net (code "66") (name "VCC") (class "Default")
      (node (ref "C10") (pin "+") (pinfunction "+_+") (pintype "passive"))
      (node (ref "C11") (pin "+") (pinfunction "+_+") (pintype "passive"))
      (node (ref "C12") (pin "2") (pinfunction "2_2") (pintype "passive"))
      (node (ref "C13") (pin "2") (pinfunction "2_2") (pintype "passive"))
      (node (ref "C14") (pin "2") (pinfunction "2_2") (pintype "passive"))
      (node (ref "C15") (pin "2") (pinfunction "2_2") (pintype "passive"))
      (node (ref "C7") (pin "+") (pinfunction "+_+") (pintype "passive"))
      (node (ref "IC1") (pin "OUT") (pinfunction "OUT_OUT") (pintype "passive"))
      (node (ref "IC2") (pin "10") (pinfunction "VDD_10") (pintype "power_in"))
      (node (ref "IC3") (pin "10") (pinfunction "VDD_10") (pintype "power_in"))
      (node (ref "J1") (pin "2") (pinfunction "2_2") (pintype "passive"))
      (node (ref "R24") (pin "2") (pinfunction "2_2") (pintype "passive"))
      (node (ref "R25") (pin "2") (pinfunction "2_2") (pintype "passive"))
      (node (ref "R26") (pin "2") (pinfunction "2_2") (pintype "passive"))
      (node (ref "R27") (pin "2") (pinfunction "2_2") (pintype "passive"))
      (node (ref "U2") (pin "14") (pinfunction "AVDD_14") (pintype "power_in"))
      (node (ref "U2") (pin "20") (pinfunction "VDD_20") (pintype "power_in"))
    )
    (net (code "67") (name "VEE") (class "Default")
      (node (ref "B1") (pin "+") (pinfunction "+_+") (pintype "passive"))
      (node (ref "C4") (pin "+") (pinfunction "+_+") (pintype "passive"))
      (node (ref "C5") (pin "+") (pinfunction "+_+") (pintype "passive"))
      (node (ref "C6") (pin "+") (pinfunction "+_+") (pintype "passive"))
      (node (ref "D14") (pin "C") (pinfunction "C_C") (pintype "passive"))
      (node (ref "D15") (pin "C") (pinfunction "C_C") (pintype "passive"))
      (node (ref "D16") (pin "C") (pinfunction "C_C") (pintype "passive"))
      (node (ref "D17") (pin "C") (pinfunction "C_C") (pintype "passive"))
      (node (ref "IC1") (pin "IN") (pinfunction "IN_IN") (pintype "input"))
      (node (ref "R28") (pin "1") (pinfunction "1_1") (pintype "passive"))
      (node (ref "RL1") (pin "2") (pinfunction "COIL2_2") (pintype "bidirectional"))
      (node (ref "RL2") (pin "2") (pinfunction "COIL2_2") (pintype "bidirectional"))
      (node (ref "RL3") (pin "2") (pinfunction "COIL2_2") (pintype "bidirectional"))
      (node (ref "X1") (pin "2") (pinfunction "S_2") (pintype "passive"))
    )
    (net (code "68") (name "V_DIS") (class "Default")
      (node (ref "IC2") (pin "3") (pinfunction "SDA_3") (pintype "input"))
      (node (ref "R24") (pin "1") (pinfunction "1_1") (pintype "passive"))
      (node (ref "U2") (pin "24") (pinfunction "SDA/2_24") (pintype "bidirectional"))
    )
    (net (code "69") (name "V_SCK") (class "Default")
      (node (ref "IC2") (pin "2") (pinfunction "SCL_2") (pintype "input"))
      (node (ref "R26") (pin "1") (pinfunction "1_1") (pintype "passive"))
      (node (ref "U2") (pin "25") (pinfunction "SCL/3_25") (pintype "bidirectional"))
    )
    (net (code "70") (name "Y") (class "Default")
      (node (ref "F2") (pin "1") (pinfunction "1_1") (pintype "passive"))
    )
    (net (code "71") (name "YA") (class "Default")
      (node (ref "CT2") (pin "2") (pinfunction "S1.2_2") (pintype "passive"))
      (node (ref "D3") (pin "A") (pinfunction "A_A") (pintype "passive"))
      (node (ref "D4") (pin "1") (pinfunction "C_1") (pintype "passive"))
      (node (ref "R21") (pin "1") (pinfunction "1_1") (pintype "passive"))
      (node (ref "U2") (pin "9") (pinfunction "15/A3_9") (pintype "bidirectional"))
    )
    (net (code "72") (name "YF") (class "Default")
      (node (ref "F2") (pin "2") (pinfunction "2_2") (pintype "passive"))
      (node (ref "R6") (pin "2") (pinfunction "2_2") (pintype "passive"))
      (node (ref "V1") (pin "1") (pinfunction "1_1") (pintype "passive"))
      (node (ref "V2") (pin "2") (pinfunction "2_2") (pintype "passive"))
    )
    (net (code "73") (name "YV") (class "Default")
      (node (ref "C2") (pin "2") (pinfunction "2_2") (pintype "passive"))
      (node (ref "D6") (pin "1") (pinfunction "C_1") (pintype "passive"))
      (node (ref "R13") (pin "1") (pinfunction "1_1") (pintype "passive"))
      (node (ref "R17") (pin "1") (pinfunction "1_1") (pintype "passive"))
      (node (ref "R18") (pin "1") (pinfunction "1_1") (pintype "passive"))
      (node (ref "U2") (pin "11") (pinfunction "17/A5_11") (pintype "bidirectional"))
    )
    (net (code "74") (name "Y_LED") (class "Default")
      (node (ref "LED5") (pin "A") (pinfunction "A_A") (pintype "passive"))
      (node (ref "LED8") (pin "A") (pinfunction "A_A") (pintype "passive"))
      (node (ref "U2") (pin "27") (pinfunction "MISO/5_27") (pintype "bidirectional"))
    )
    (net (code "75") (name "unconnected-(IC2-DIG4-Pad7)") (class "Default")
      (node (ref "IC2") (pin "7") (pinfunction "DIG4_7") (pintype "bidirectional"))
    )
    (net (code "76") (name "unconnected-(IC3-DIG4-Pad7)") (class "Default")
      (node (ref "IC3") (pin "7") (pinfunction "DIG4_7") (pintype "bidirectional"))
    )
  )
)
